# interface.net
KiCad netlist of a schematic drawn in Altium Designer
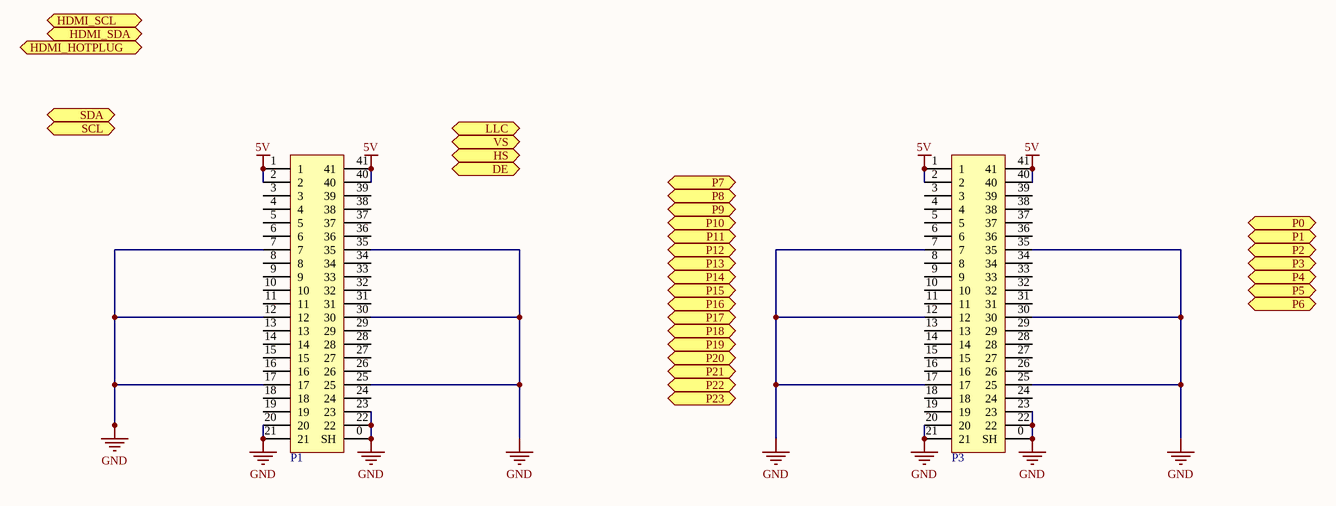
[diagram p0: interface.SchDoc]

(export (version "E")
  (design (tool "Eeschema 10.0.6"))
  (components
    (comp (ref "P1") (value "DF9-41S") (footprint "DF9-41S") (libsource (lib "cyusb3014") (part "DF9-41S")))
    (comp (ref "P3") (value "DF9-41S") (footprint "DF9-41S") (libsource (lib "cyusb3014") (part "DF9-41S")))
  )
  (nets
    (net (code "34") (name "5V") (class "Default")
      (node (ref "P1") (pin "1") (pinfunction "1_1") (pintype "passive"))
      (node (ref "P1") (pin "2") (pinfunction "2_2") (pintype "passive"))
      (node (ref "P1") (pin "40") (pinfunction "40_40") (pintype "passive"))
      (node (ref "P1") (pin "41") (pinfunction "41_41") (pintype "passive"))
      (node (ref "P3") (pin "1") (pinfunction "1_1") (pintype "passive"))
      (node (ref "P3") (pin "2") (pinfunction "2_2") (pintype "passive"))
      (node (ref "P3") (pin "40") (pinfunction "40_40") (pintype "passive"))
      (node (ref "P3") (pin "41") (pinfunction "41_41") (pintype "passive"))
    )
    (net (code "35") (name "GND") (class "Default")
      (node (ref "P1") (pin "0") (pinfunction "SH_0") (pintype "passive"))
      (node (ref "P1") (pin "12") (pinfunction "12_12") (pintype "passive"))
      (node (ref "P1") (pin "17") (pinfunction "17_17") (pintype "passive"))
      (node (ref "P1") (pin "20") (pinfunction "20_20") (pintype "passive"))
      (node (ref "P1") (pin "21") (pinfunction "21_21") (pintype "passive"))
      (node (ref "P1") (pin "22") (pinfunction "22_22") (pintype "passive"))
      (node (ref "P1") (pin "23") (pinfunction "23_23") (pintype "passive"))
      (node (ref "P1") (pin "25") (pinfunction "25_25") (pintype "passive"))
      (node (ref "P1") (pin "30") (pinfunction "30_30") (pintype "passive"))
      (node (ref "P1") (pin "35") (pinfunction "35_35") (pintype "passive"))
      (node (ref "P1") (pin "7") (pinfunction "7_7") (pintype "passive"))
      (node (ref "P3") (pin "0") (pinfunction "SH_0") (pintype "passive"))
      (node (ref "P3") (pin "12") (pinfunction "12_12") (pintype "passive"))
      (node (ref "P3") (pin "17") (pinfunction "17_17") (pintype "passive"))
      (node (ref "P3") (pin "20") (pinfunction "20_20") (pintype "passive"))
      (node (ref "P3") (pin "21") (pinfunction "21_21") (pintype "passive"))
      (node (ref "P3") (pin "22") (pinfunction "22_22") (pintype "passive"))
      (node (ref "P3") (pin "23") (pinfunction "23_23") (pintype "passive"))
      (node (ref "P3") (pin "25") (pinfunction "25_25") (pintype "passive"))
      (node (ref "P3") (pin "30") (pinfunction "30_30") (pintype "passive"))
      (node (ref "P3") (pin "35") (pinfunction "35_35") (pintype "passive"))
      (node (ref "P3") (pin "7") (pinfunction "7_7") (pintype "passive"))
    )
    (net (code "36") (name "unconnected-(P1-Pad3)") (class "Default")
      (node (ref "P1") (pin "3") (pinfunction "3_3") (pintype "passive"))
    )
    (net (code "37") (name "unconnected-(P1-Pad4)") (class "Default")
      (node (ref "P1") (pin "4") (pinfunction "4_4") (pintype "passive"))
    )
    (net (code "38") (name "unconnected-(P1-Pad5)") (class "Default")
      (node (ref "P1") (pin "5") (pinfunction "5_5") (pintype "passive"))
    )
    (net (code "39") (name "unconnected-(P1-Pad6)") (class "Default")
      (node (ref "P1") (pin "6") (pinfunction "6_6") (pintype "passive"))
    )
    (net (code "40") (name "unconnected-(P1-Pad8)") (class "Default")
      (node (ref "P1") (pin "8") (pinfunction "8_8") (pintype "passive"))
    )
    (net (code "41") (name "unconnected-(P1-Pad9)") (class "Default")
      (node (ref "P1") (pin "9") (pinfunction "9_9") (pintype "passive"))
    )
    (net (code "42") (name "unconnected-(P1-Pad10)") (class "Default")
      (node (ref "P1") (pin "10") (pinfunction "10_10") (pintype "passive"))
    )
    (net (code "43") (name "unconnected-(P1-Pad11)") (class "Default")
      (node (ref "P1") (pin "11") (pinfunction "11_11") (pintype "passive"))
    )
    (net (code "44") (name "unconnected-(P1-Pad13)") (class "Default")
      (node (ref "P1") (pin "13") (pinfunction "13_13") (pintype "passive"))
    )
    (net (code "45") (name "unconnected-(P1-Pad14)") (class "Default")
      (node (ref "P1") (pin "14") (pinfunction "14_14") (pintype "passive"))
    )
    (net (code "46") (name "unconnected-(P1-Pad15)") (class "Default")
      (node (ref "P1") (pin "15") (pinfunction "15_15") (pintype "passive"))
    )
    (net (code "47") (name "unconnected-(P1-Pad16)") (class "Default")
      (node (ref "P1") (pin "16") (pinfunction "16_16") (pintype "passive"))
    )
    (net (code "48") (name "unconnected-(P1-Pad18)") (class "Default")
      (node (ref "P1") (pin "18") (pinfunction "18_18") (pintype "passive"))
    )
    (net (code "49") (name "unconnected-(P1-Pad19)") (class "Default")
      (node (ref "P1") (pin "19") (pinfunction "19_19") (pintype "passive"))
    )
    (net (code "50") (name "unconnected-(P1-Pad24)") (class "Default")
      (node (ref "P1") (pin "24") (pinfunction "24_24") (pintype "passive"))
    )
    (net (code "51") (name "unconnected-(P1-Pad26)") (class "Default")
      (node (ref "P1") (pin "26") (pinfunction "26_26") (pintype "passive"))
    )
    (net (code "52") (name "unconnected-(P1-Pad27)") (class "Default")
      (node (ref "P1") (pin "27") (pinfunction "27_27") (pintype "passive"))
    )
    (net (code "53") (name "unconnected-(P1-Pad28)") (class "Default")
      (node (ref "P1") (pin "28") (pinfunction "28_28") (pintype "passive"))
    )
    (net (code "54") (name "unconnected-(P1-Pad29)") (class "Default")
      (node (ref "P1") (pin "29") (pinfunction "29_29") (pintype "passive"))
    )
    (net (code "55") (name "unconnected-(P1-Pad31)") (class "Default")
      (node (ref "P1") (pin "31") (pinfunction "31_31") (pintype "passive"))
    )
    (net (code "56") (name "unconnected-(P1-Pad32)") (class "Default")
      (node (ref "P1") (pin "32") (pinfunction "32_32") (pintype "passive"))
    )
    (net (code "57") (name "unconnected-(P1-Pad33)") (class "Default")
      (node (ref "P1") (pin "33") (pinfunction "33_33") (pintype "passive"))
    )
    (net (code "58") (name "unconnected-(P1-Pad34)") (class "Default")
      (node (ref "P1") (pin "34") (pinfunction "34_34") (pintype "passive"))
    )
    (net (code "59") (name "unconnected-(P1-Pad36)") (class "Default")
      (node (ref "P1") (pin "36") (pinfunction "36_36") (pintype "passive"))
    )
    (net (code "60") (name "unconnected-(P1-Pad37)") (class "Default")
      (node (ref "P1") (pin "37") (pinfunction "37_37") (pintype "passive"))
    )
    (net (code "61") (name "unconnected-(P1-Pad38)") (class "Default")
      (node (ref "P1") (pin "38") (pinfunction "38_38") (pintype "passive"))
    )
    (net (code "62") (name "unconnected-(P1-Pad39)") (class "Default")
      (node (ref "P1") (pin "39") (pinfunction "39_39") (pintype "passive"))
    )
    (net (code "63") (name "unconnected-(P3-Pad3)") (class "Default")
      (node (ref "P3") (pin "3") (pinfunction "3_3") (pintype "passive"))
    )
    (net (code "64") (name "unconnected-(P3-Pad4)") (class "Default")
      (node (ref "P3") (pin "4") (pinfunction "4_4") (pintype "passive"))
    )
    (net (code "65") (name "unconnected-(P3-Pad5)") (class "Default")
      (node (ref "P3") (pin "5") (pinfunction "5_5") (pintype "passive"))
    )
    (net (code "66") (name "unconnected-(P3-Pad6)") (class "Default")
      (node (ref "P3") (pin "6") (pinfunction "6_6") (pintype "passive"))
    )
    (net (code "67") (name "unconnected-(P3-Pad8)") (class "Default")
      (node (ref "P3") (pin "8") (pinfunction "8_8") (pintype "passive"))
    )
    (net (code "68") (name "unconnected-(P3-Pad9)") (class "Default")
      (node (ref "P3") (pin "9") (pinfunction "9_9") (pintype "passive"))
    )
    (net (code "69") (name "unconnected-(P3-Pad10)") (class "Default")
      (node (ref "P3") (pin "10") (pinfunction "10_10") (pintype "passive"))
    )
    (net (code "70") (name "unconnected-(P3-Pad11)") (class "Default")
      (node (ref "P3") (pin "11") (pinfunction "11_11") (pintype "passive"))
    )
    (net (code "71") (name "unconnected-(P3-Pad13)") (class "Default")
      (node (ref "P3") (pin "13") (pinfunction "13_13") (pintype "passive"))
    )
    (net (code "72") (name "unconnected-(P3-Pad14)") (class "Default")
      (node (ref "P3") (pin "14") (pinfunction "14_14") (pintype "passive"))
    )
    (net (code "73") (name "unconnected-(P3-Pad15)") (class "Default")
      (node (ref "P3") (pin "15") (pinfunction "15_15") (pintype "passive"))
    )
    (net (code "74") (name "unconnected-(P3-Pad16)") (class "Default")
      (node (ref "P3") (pin "16") (pinfunction "16_16") (pintype "passive"))
    )
    (net (code "75") (name "unconnected-(P3-Pad18)") (class "Default")
      (node (ref "P3") (pin "18") (pinfunction "18_18") (pintype "passive"))
    )
    (net (code "76") (name "unconnected-(P3-Pad19)") (class "Default")
      (node (ref "P3") (pin "19") (pinfunction "19_19") (pintype "passive"))
    )
    (net (code "77") (name "unconnected-(P3-Pad24)") (class "Default")
      (node (ref "P3") (pin "24") (pinfunction "24_24") (pintype "passive"))
    )
    (net (code "78") (name "unconnected-(P3-Pad26)") (class "Default")
      (node (ref "P3") (pin "26") (pinfunction "26_26") (pintype "passive"))
    )
    (net (code "79") (name "unconnected-(P3-Pad27)") (class "Default")
      (node (ref "P3") (pin "27") (pinfunction "27_27") (pintype "passive"))
    )
    (net (code "80") (name "unconnected-(P3-Pad28)") (class "Default")
      (node (ref "P3") (pin "28") (pinfunction "28_28") (pintype "passive"))
    )
    (net (code "81") (name "unconnected-(P3-Pad29)") (class "Default")
      (node (ref "P3") (pin "29") (pinfunction "29_29") (pintype "passive"))
    )
    (net (code "82") (name "unconnected-(P3-Pad31)") (class "Default")
      (node (ref "P3") (pin "31") (pinfunction "31_31") (pintype "passive"))
    )
    (net (code "83") (name "unconnected-(P3-Pad32)") (class "Default")
      (node (ref "P3") (pin "32") (pinfunction "32_32") (pintype "passive"))
    )
    (net (code "84") (name "unconnected-(P3-Pad33)") (class "Default")
      (node (ref "P3") (pin "33") (pinfunction "33_33") (pintype "passive"))
    )
    (net (code "85") (name "unconnected-(P3-Pad34)") (class "Default")
      (node (ref "P3") (pin "34") (pinfunction "34_34") (pintype "passive"))
    )
    (net (code "86") (name "unconnected-(P3-Pad36)") (class "Default")
      (node (ref "P3") (pin "36") (pinfunction "36_36") (pintype "passive"))
    )
    (net (code "87") (name "unconnected-(P3-Pad37)") (class "Default")
      (node (ref "P3") (pin "37") (pinfunction "37_37") (pintype "passive"))
    )
    (net (code "88") (name "unconnected-(P3-Pad38)") (class "Default")
      (node (ref "P3") (pin "38") (pinfunction "38_38") (pintype "passive"))
    )
    (net (code "89") (name "unconnected-(P3-Pad39)") (class "Default")
      (node (ref "P3") (pin "39") (pinfunction "39_39") (pintype "passive"))
    )
  )
)
